# PSU.net
KiCad netlist of a schematic drawn in Altium Designer
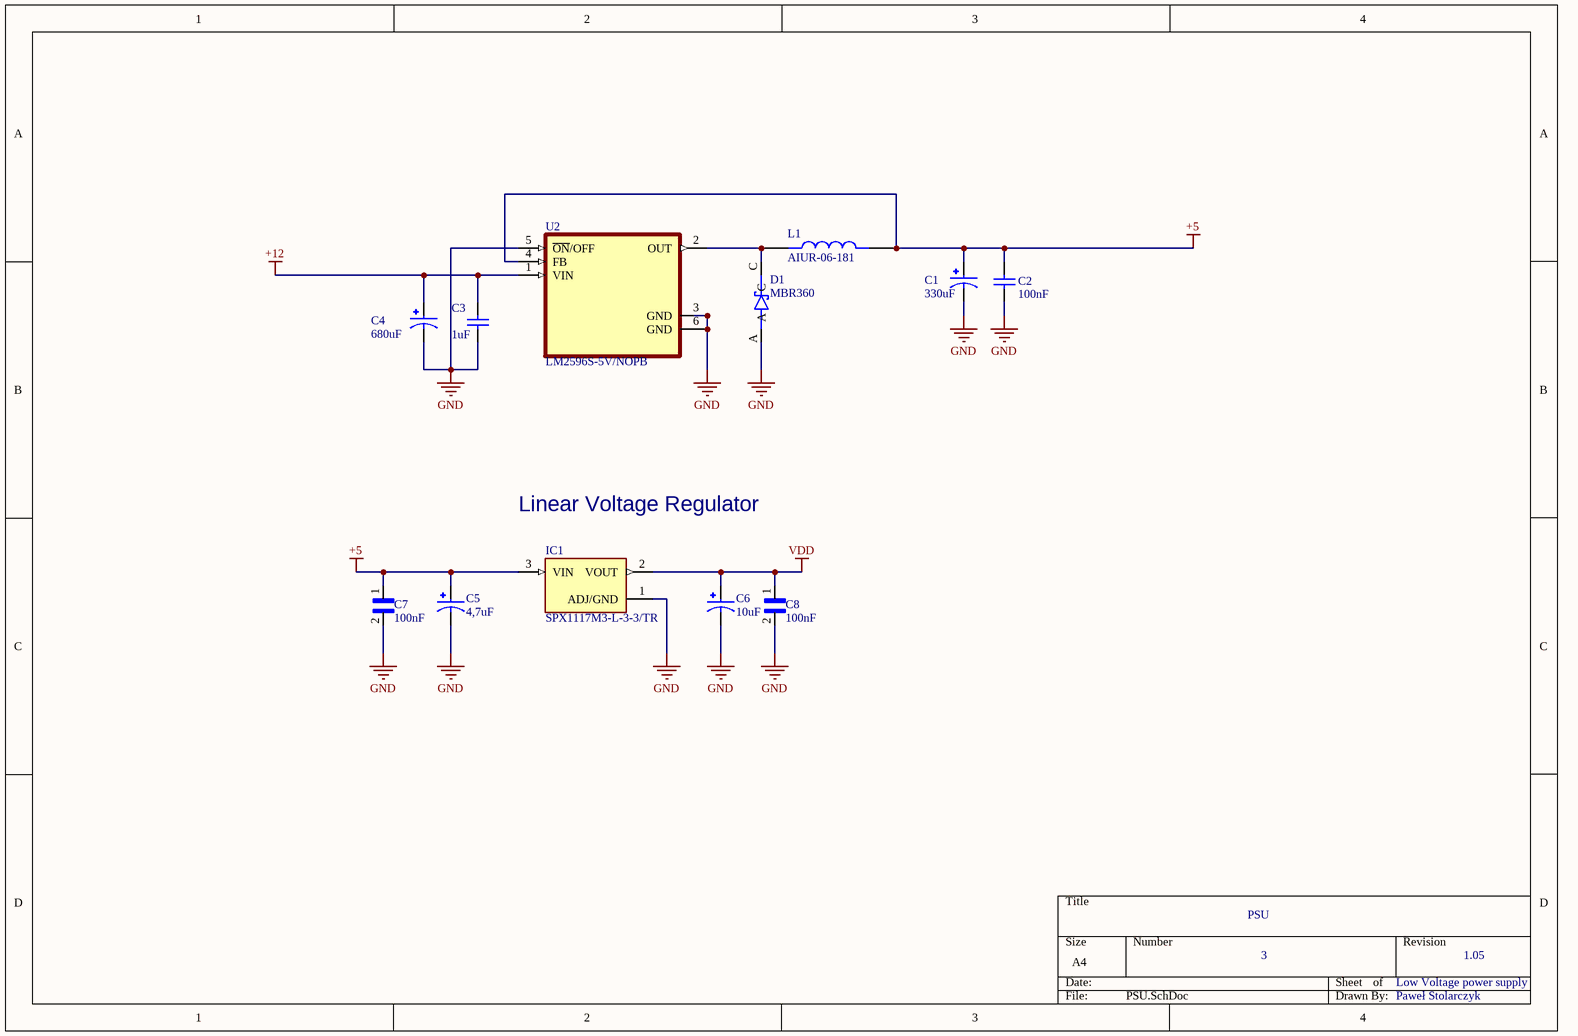
[diagram p0: PSU.SchDoc]

(export (version "E")
  (design (tool "Eeschema 10.0.6"))
  (components
    (comp (ref "C1")
      (value "330uF")
      (footprint "CAP_16SVP330M")
      (fields (field (name "MP") "16SVP330M"))
      (libsource (lib "16SVP330M") (part "16SVP330M"))
    )
    (comp (ref "C2")
      (value "100nF")
      (footprint "0402")
      (description "Capacitor")
      (fields (field (name "Comment") "Cap") (field (name "PUBLISHER") "Altium Limited"))
      (libsource (lib "Miscellaneous Devices") (part "Cap"))
    )
    (comp (ref "C3")
      (value "1uF")
      (footprint "0402")
      (description "Capacitor")
      (fields (field (name "Comment") "Cap") (field (name "PUBLISHER") "Altium Limited"))
      (libsource (lib "Miscellaneous Devices") (part "Cap"))
    )
    (comp (ref "C4")
      (value "680uF")
      (footprint "CAP_16SVPC100M")
      (fields (field (name "MP") "16SVPC100M"))
      (libsource (lib "16SVPC100M") (part "16SVPC100M"))
    )
    (comp (ref "C5")
      (value "4,7uF")
      (footprint "CAP_EEE1CA100SR")
      (description "10ÂµF 16V Aluminum Electrolytic Capacitors Radial, Can - SMD 2000 Hrs @ 85Â°C")
      (fields (field (name "MF") "Panasonic") (field (name "DIGI-KEY_PART_NUMBER") "PCE3878CT-ND"))
      (libsource (lib "EEE1CA100SR") (part "EEE1CA100SR"))
    )
    (comp (ref "C6")
      (value "10uF")
      (footprint "CAP_EEE1CA100SR")
      (description "10ÂµF 16V Aluminum Electrolytic Capacitors Radial, Can - SMD 2000 Hrs @ 85Â°C")
      (fields (field (name "MF") "Panasonic") (field (name "DIGI-KEY_PART_NUMBER") "PCE3878CT-ND"))
      (libsource (lib "EEE1CA100SR") (part "EEE1CA100SR"))
    )
    (comp (ref "C7")
      (value "100nF")
      (footprint "CAPC1608X90N")
      (description "0.1ÂµF Â±5% 16V Ceramic Capacitor X7R 0603 (1608 Metric)")
      (fields (field (name "MP") "C0603C104J4RAC") (field (name "MF") "KEMET"))
      (libsource (lib "C0603C104J4RAC") (part "C0603C104J4RAC"))
    )
    (comp (ref "C8")
      (value "100nF")
      (footprint "CAPC1608X90N")
      (description "0.1ÂµF Â±5% 16V Ceramic Capacitor X7R 0603 (1608 Metric)")
      (fields (field (name "MP") "C0603C104J4RAC") (field (name "MF") "KEMET"))
      (libsource (lib "C0603C104J4RAC") (part "C0603C104J4RAC"))
    )
    (comp (ref "D1")
      (value "MBR360")
      (footprint "DIOAD1950W125L950D560")
      (description "Diode Schottky 60V 3A Through Hole DO-201AD")
      (fields (field (name "MF") "ON Semiconductor") (field (name "MP") "MBR360G"))
      (libsource (lib "MBR360") (part "MBR360"))
    )
    (comp (ref "IC1")
      (value "SPX1117M3-L-3-3/TR")
      (footprint "SOT230P700X180-3N")
      (description "Linear Voltage Regulator IC Positive Fixed 1 Output 800mA SOT-223")
      (fields (field (name "MF") "MaxLinear, Inc."))
      (libsource (lib "SPX1117M3-L-3-3_TR") (part "SPX1117M3-L-3-3/TR"))
    )
    (comp (ref "L1")
      (value "AIUR-06-181")
      (footprint "INDRD500W70D850H750")
      (description "FIXED IND 180UH 1.6A 228 MOHM TH")
      (fields (field (name "MF") "Abracon LLC"))
      (libsource (lib "AIUR-06-181") (part "AIUR-06-181"))
    )
    (comp (ref "U2")
      (value "LM2596S-5V/NOPB")
      (footprint "VREG_LM2596S-ADJ/NOPB")
      (description "SIMPLE SWITCHER&reg; 4.5V to 40V, 3A Low Component Count Step-Down Regulator")
      (fields (field (name "MF") "Texas Instruments") (field (name "MP") "LM2596S-ADJ/NOPB"))
      (libsource (lib "LM2596S-ADJ_NOPB") (part "LM2596S-ADJ/NOPB"))
    )
  )
  (nets
    (net (code "1") (name "+5") (class "Default")
      (node (ref "C1") (pin "1") (pinfunction "1_1") (pintype "passive"))
      (node (ref "C2") (pin "2") (pinfunction "2_2") (pintype "passive"))
      (node (ref "C5") (pin "1") (pinfunction "1_1") (pintype "passive"))
      (node (ref "C7") (pin "1") (pinfunction "1_1") (pintype "passive"))
      (node (ref "IC1") (pin "3") (pinfunction "VIN_3") (pintype "input"))
      (node (ref "L1") (pin "2") (pinfunction "2_2") (pintype "passive"))
      (node (ref "U2") (pin "4") (pinfunction "FB_4") (pintype "input"))
    )
    (net (code "2") (name "+12") (class "Default")
      (node (ref "C3") (pin "2") (pinfunction "2_2") (pintype "passive"))
      (node (ref "C4") (pin "1") (pinfunction "1_1") (pintype "passive"))
      (node (ref "U2") (pin "1") (pinfunction "VIN_1") (pintype "input"))
    )
    (net (code "3") (name "GND") (class "Default")
      (node (ref "C1") (pin "2") (pinfunction "2_2") (pintype "passive"))
      (node (ref "C2") (pin "1") (pinfunction "1_1") (pintype "passive"))
      (node (ref "C3") (pin "1") (pinfunction "1_1") (pintype "passive"))
      (node (ref "C4") (pin "2") (pinfunction "2_2") (pintype "passive"))
      (node (ref "C5") (pin "2") (pinfunction "2_2") (pintype "passive"))
      (node (ref "C6") (pin "2") (pinfunction "2_2") (pintype "passive"))
      (node (ref "C7") (pin "2") (pinfunction "2_2") (pintype "passive"))
      (node (ref "C8") (pin "2") (pinfunction "2_2") (pintype "passive"))
      (node (ref "D1") (pin "A") (pinfunction "A_A") (pintype "passive"))
      (node (ref "IC1") (pin "1") (pinfunction "ADJ/GND_1") (pintype "power_in"))
      (node (ref "U2") (pin "3") (pinfunction "GND_3") (pintype "power_in"))
      (node (ref "U2") (pin "5") (pinfunction "~{ON}/OFF_5") (pintype "input"))
      (node (ref "U2") (pin "6") (pinfunction "GND_6") (pintype "power_in"))
    )
    (net (code "4") (name "Net-(U2-OUT)") (class "Default")
      (node (ref "D1") (pin "C") (pinfunction "C_C") (pintype "passive"))
      (node (ref "L1") (pin "1") (pinfunction "1_1") (pintype "passive"))
      (node (ref "U2") (pin "2") (pinfunction "OUT_2") (pintype "output"))
    )
    (net (code "5") (name "VDD") (class "Default")
      (node (ref "C6") (pin "1") (pinfunction "1_1") (pintype "passive"))
      (node (ref "C8") (pin "1") (pinfunction "1_1") (pintype "passive"))
      (node (ref "IC1") (pin "2") (pinfunction "VOUT_2") (pintype "output"))
    )
  )
)
